# WBD_01.net
KiCad netlist of a schematic drawn in EAGLE
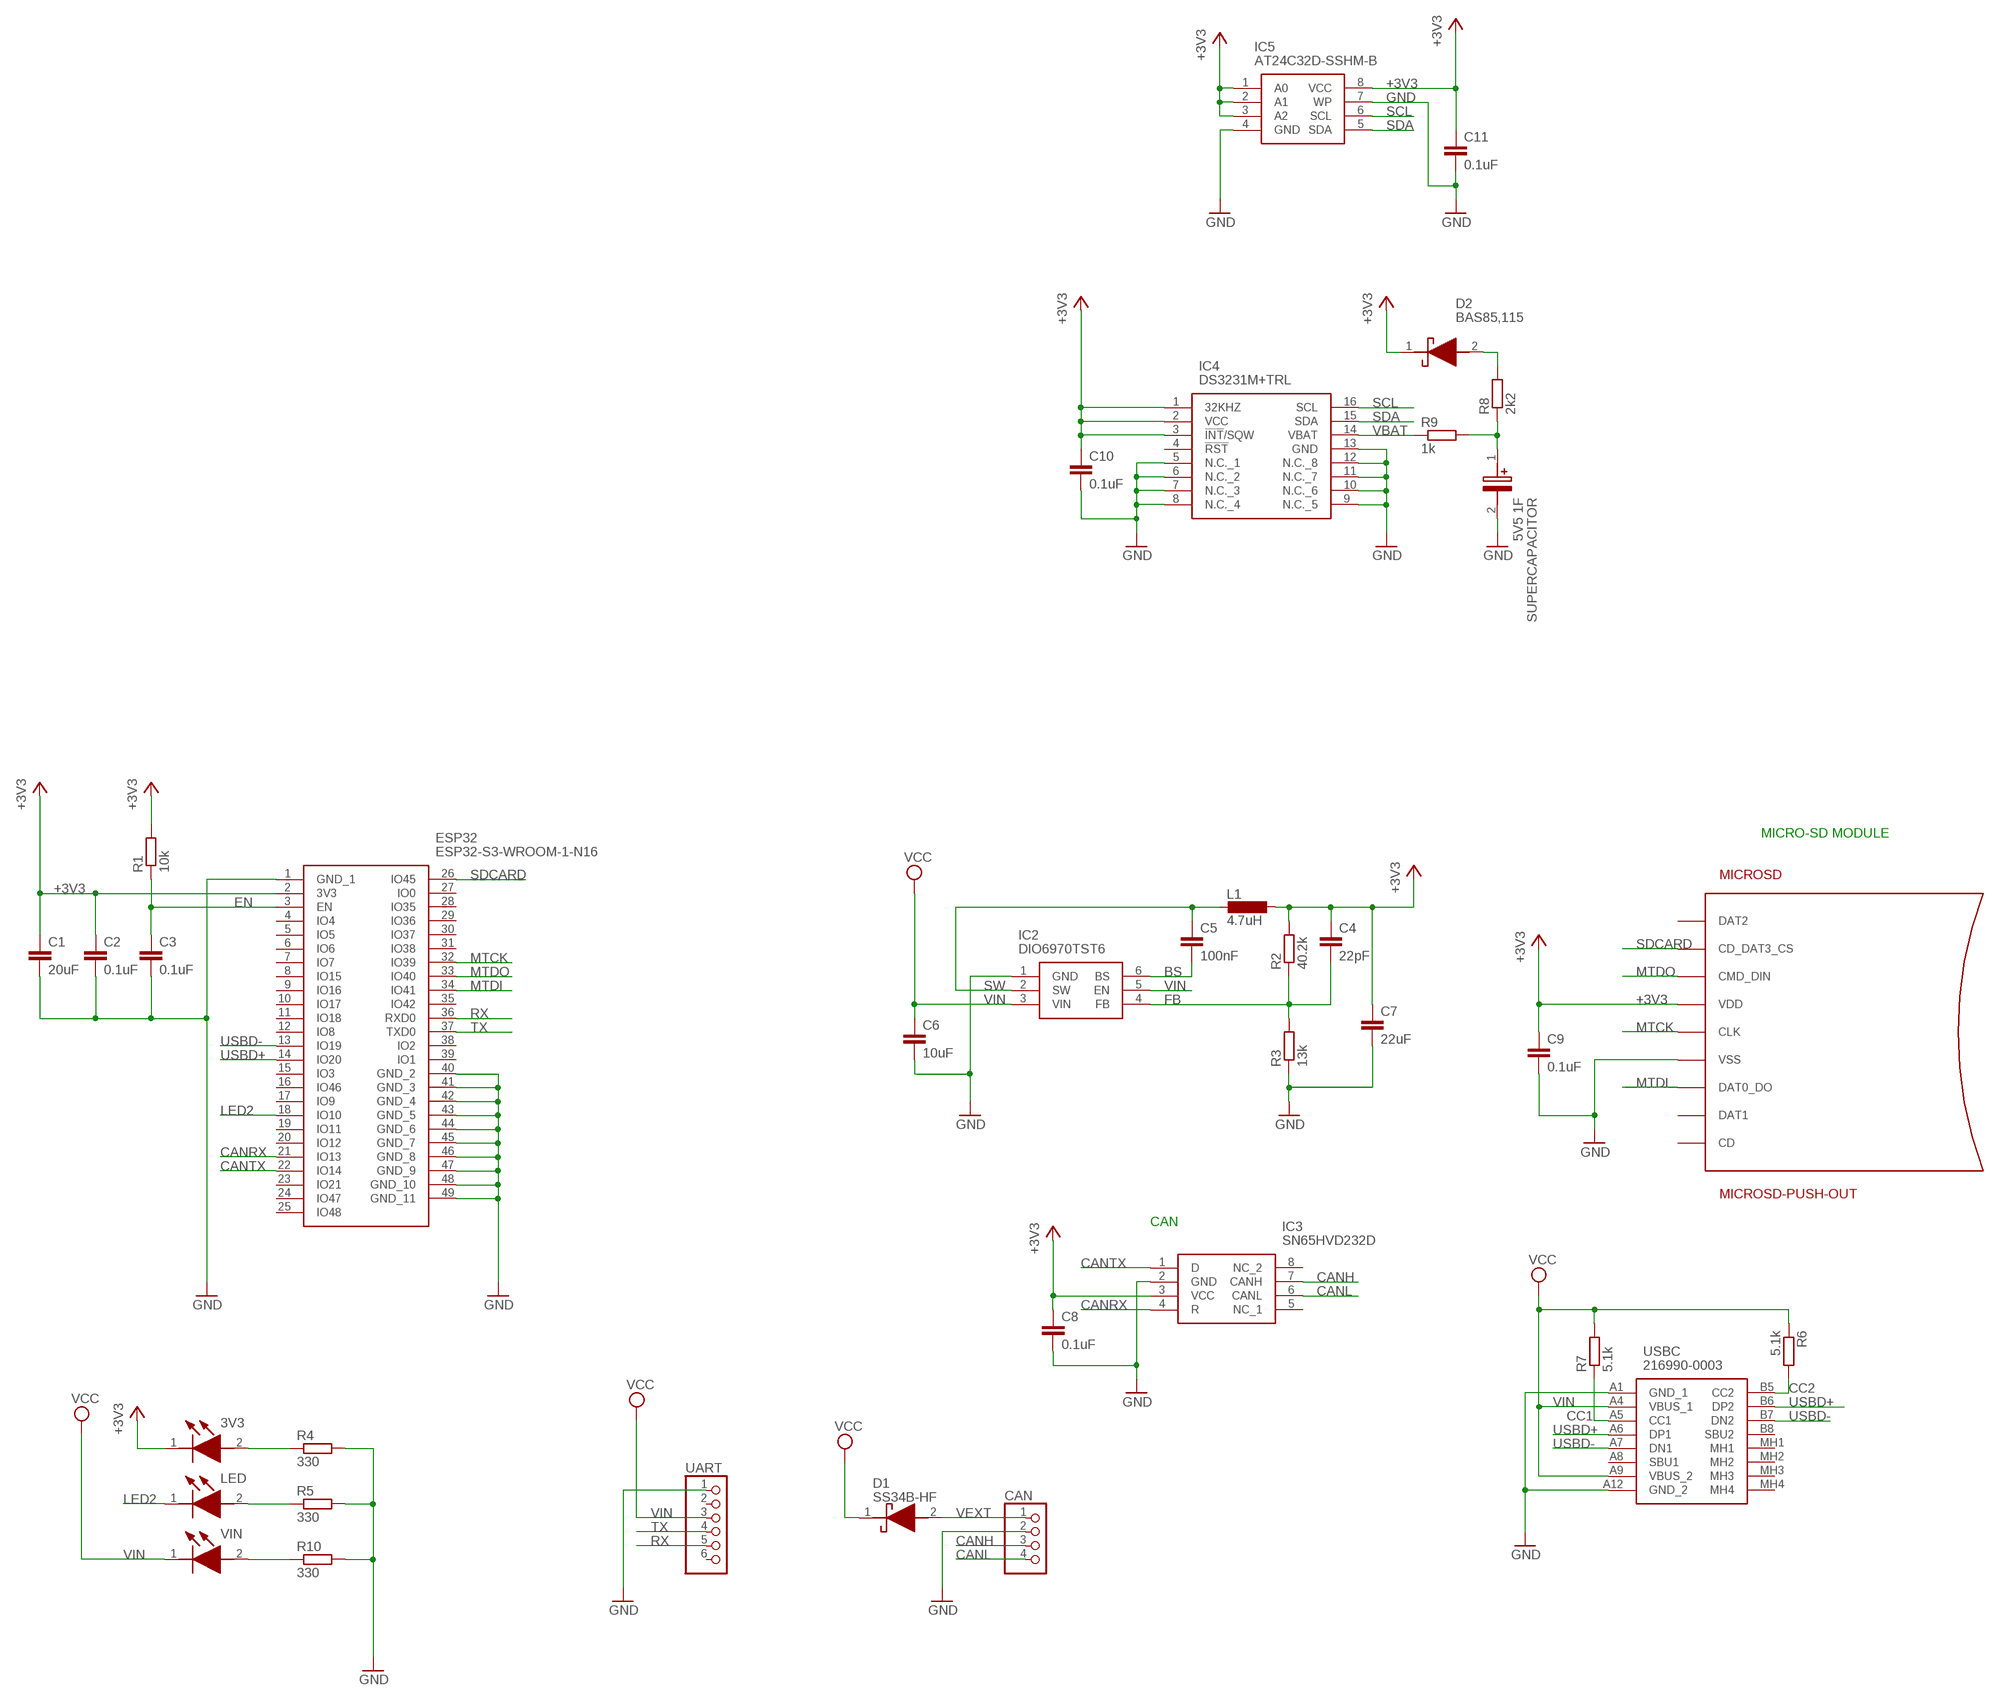
[diagram p0: schematic, sheet 1]

(export (version "E")
  (design (tool "Eeschema 10.0.6"))
  (components
    (comp (ref "3V3")
      (value "150060GS75000")
      (footprint "eagle-import:LEDC1608X80N")
      (fields (field (name "MOUSER_PART_NUMBER") "710-150060GS75000"))
      (libsource (lib "eagle-import") (part "150060GS75000"))
    )
    (comp (ref "C1")
      (value "20uF")
      (footprint "eagle-import:C0603")
      (libsource (lib "eagle-import") (part "C-EUC0603"))
    )
    (comp (ref "C2")
      (value "0.1uF")
      (footprint "eagle-import:C0603")
      (libsource (lib "eagle-import") (part "C-EUC0603"))
    )
    (comp (ref "C3")
      (value "0.1uF")
      (footprint "eagle-import:C0603")
      (libsource (lib "eagle-import") (part "C-EUC0603"))
    )
    (comp (ref "C4")
      (value "22pF")
      (footprint "eagle-import:C0603")
      (libsource (lib "eagle-import") (part "C-EUC0603"))
    )
    (comp (ref "C5")
      (value "100nF")
      (footprint "eagle-import:C0603")
      (libsource (lib "eagle-import") (part "C-EUC0603"))
    )
    (comp (ref "C6")
      (value "10uF")
      (footprint "eagle-import:C0603")
      (libsource (lib "eagle-import") (part "C-EUC0603"))
    )
    (comp (ref "C7")
      (value "22uF")
      (footprint "eagle-import:C0603")
      (libsource (lib "eagle-import") (part "C-EUC0603"))
    )
    (comp (ref "C8")
      (value "0.1uF")
      (footprint "eagle-import:C0603")
      (libsource (lib "eagle-import") (part "C-EUC0603"))
    )
    (comp (ref "C9")
      (value "0.1uF")
      (footprint "eagle-import:C0603")
      (libsource (lib "eagle-import") (part "C-EUC0603"))
    )
    (comp (ref "C10")
      (value "0.1uF")
      (footprint "eagle-import:C0603")
      (libsource (lib "eagle-import") (part "C-EUC0603"))
    )
    (comp (ref "C11")
      (value "0.1uF")
      (footprint "eagle-import:C0603")
      (libsource (lib "eagle-import") (part "C-EUC0603"))
    )
    (comp (ref "CAN")
      (value "PINHD-1X4M")
      (footprint "eagle-import:1X04M")
      (libsource (lib "eagle-import") (part "PINHD-1X4M"))
    )
    (comp (ref "D1")
      (value "SS34B-HF")
      (footprint "eagle-import:DIOM5336X320N")
      (fields (field (name "MOUSER_PART_NUMBER") "750-SS34B-HF"))
      (libsource (lib "eagle-import") (part "SS34B-HF"))
    )
    (comp (ref "D2")
      (value "BAS85,115")
      (footprint "eagle-import:BAS85115")
      (fields (field (name "MOUSER_PART_NUMBER") "771-BAS85-T/R"))
      (libsource (lib "eagle-import") (part "BAS85,115"))
    )
    (comp (ref "ESP32")
      (value "ESP32-S3-WROOM-1-N16")
      (footprint "eagle-import:ESP32S3WROOM1N16")
      (fields (field (name "MOUSER_PART_NUMBER") "356-ESP32S3WROOM1N16"))
      (libsource (lib "eagle-import") (part "ESP32-S3-WROOM-1-N16"))
    )
    (comp (ref "IC2")
      (value "DIO6970TST6")
      (footprint "eagle-import:SOT95P280X90-6N")
      (fields (field (name "MOUSER_PART_NUMBER") "453-DIO6970ST6"))
      (libsource (lib "eagle-import") (part "DIO6970TST6"))
    )
    (comp (ref "IC3")
      (value "SN65HVD232D")
      (footprint "eagle-import:SOIC127P600X175-8N")
      (fields (field (name "MOUSER_PART_NUMBER") "595-SN65HVD232D"))
      (libsource (lib "eagle-import") (part "SN65HVD232D"))
    )
    (comp (ref "IC4")
      (value "DS3231M+TRL")
      (footprint "eagle-import:SOIC127P1032X265-16N")
      (fields (field (name "MOUSER_PART_NUMBER") "700-DS3231M+TRL"))
      (libsource (lib "eagle-import") (part "DS3231M+TRL"))
    )
    (comp (ref "IC5")
      (value "AT24C32D-SSHM-B")
      (footprint "eagle-import:SOIC127P600X175-8N")
      (fields (field (name "MOUSER_PART_NUMBER") "556-AT24C32D-SSHM-B"))
      (libsource (lib "eagle-import") (part "AT24C32D-SSHM-B"))
    )
    (comp (ref "L1")
      (value "4.7uH")
      (footprint "eagle-import:L5650M")
      (libsource (lib "eagle-import") (part "L-EUL5650M"))
    )
    (comp (ref "LED")
      (value "150060GS75000")
      (footprint "eagle-import:LEDC1608X80N")
      (fields (field (name "MOUSER_PART_NUMBER") "710-150060GS75000"))
      (libsource (lib "eagle-import") (part "150060GS75000"))
    )
    (comp (ref "MICROSD")
      (value "MICROSD-PUSH-OUT")
      (footprint "eagle-import:MICROSD-PUSH-OUT")
      (libsource (lib "eagle-import") (part "MICROSD-PUSH-OUT"))
    )
    (comp (ref "R1")
      (value "10k")
      (footprint "eagle-import:R0603")
      (libsource (lib "eagle-import") (part "R-EU_R0603"))
    )
    (comp (ref "R2")
      (value "40.2k")
      (footprint "eagle-import:R0603")
      (libsource (lib "eagle-import") (part "R-EU_R0603"))
    )
    (comp (ref "R3")
      (value "13k")
      (footprint "eagle-import:R0603")
      (libsource (lib "eagle-import") (part "R-EU_R0603"))
    )
    (comp (ref "R4")
      (value "330")
      (footprint "eagle-import:R0603")
      (libsource (lib "eagle-import") (part "R-EU_R0603"))
    )
    (comp (ref "R5")
      (value "330")
      (footprint "eagle-import:R0603")
      (libsource (lib "eagle-import") (part "R-EU_R0603"))
    )
    (comp (ref "R6")
      (value "5.1k")
      (footprint "eagle-import:R0603")
      (libsource (lib "eagle-import") (part "R-EU_R0603"))
    )
    (comp (ref "R7")
      (value "5.1k")
      (footprint "eagle-import:R0603")
      (libsource (lib "eagle-import") (part "R-EU_R0603"))
    )
    (comp (ref "R8")
      (value "2k2")
      (footprint "eagle-import:R0603")
      (libsource (lib "eagle-import") (part "R-EU_R0603"))
    )
    (comp (ref "R9")
      (value "1k")
      (footprint "eagle-import:R0603")
      (libsource (lib "eagle-import") (part "R-EU_R0603"))
    )
    (comp (ref "R10")
      (value "330")
      (footprint "eagle-import:R0603")
      (libsource (lib "eagle-import") (part "R-EU_R0603"))
    )
    (comp (ref "SUPERCAPACITOR")
      (value "5V5 1F")
      (footprint "eagle-import:CAPPRD500W130D2150H800")
      (fields
        (field (name "MANUFACTURER_PART_NUMBER") "DB-5R5D105T")
        (field (name "MOUSER_PART_NUMBER") "555-DB-5R5D105T")
      )
      (libsource (lib "eagle-import") (part "DB-5R5D105T"))
    )
    (comp (ref "UART")
      (value "PINHD-1X6M")
      (footprint "eagle-import:1X06M")
      (libsource (lib "eagle-import") (part "PINHD-1X6M"))
    )
    (comp (ref "USBC")
      (value "216990-0003")
      (footprint "eagle-import:2169900003")
      (fields (field (name "MOUSER_PART_NUMBER") "538-216990-0003"))
      (libsource (lib "eagle-import") (part "216990-0003"))
    )
    (comp (ref "VIN")
      (value "150060GS75000")
      (footprint "eagle-import:LEDC1608X80N")
      (fields (field (name "MOUSER_PART_NUMBER") "710-150060GS75000"))
      (libsource (lib "eagle-import") (part "150060GS75000"))
    )
  )
  (nets
    (net (code "1") (name "+3V3") (class "Default")
      (node (ref "3V3") (pin "1") (pinfunction "K_1") (pintype "bidirectional"))
      (node (ref "C1") (pin "1") (pinfunction "1_1") (pintype "passive"))
      (node (ref "C10") (pin "1") (pinfunction "1_1") (pintype "passive"))
      (node (ref "C11") (pin "1") (pinfunction "1_1") (pintype "passive"))
      (node (ref "C2") (pin "1") (pinfunction "1_1") (pintype "passive"))
      (node (ref "C4") (pin "1") (pinfunction "1_1") (pintype "passive"))
      (node (ref "C7") (pin "1") (pinfunction "1_1") (pintype "passive"))
      (node (ref "C8") (pin "1") (pinfunction "1_1") (pintype "passive"))
      (node (ref "C9") (pin "1") (pinfunction "1_1") (pintype "passive"))
      (node (ref "D2") (pin "1") (pinfunction "K_1") (pintype "bidirectional"))
      (node (ref "ESP32") (pin "2") (pinfunction "3V3_2") (pintype "bidirectional"))
      (node (ref "IC3") (pin "3") (pinfunction "VCC_3") (pintype "bidirectional"))
      (node (ref "IC4") (pin "1") (pinfunction "32KHZ_1") (pintype "bidirectional"))
      (node (ref "IC4") (pin "2") (pinfunction "VCC_2") (pintype "bidirectional"))
      (node (ref "IC4") (pin "3") (pinfunction "~{INT}/SQW_3") (pintype "bidirectional"))
      (node (ref "IC5") (pin "1") (pinfunction "A0_1") (pintype "bidirectional"))
      (node (ref "IC5") (pin "2") (pinfunction "A1_2") (pintype "bidirectional"))
      (node (ref "IC5") (pin "3") (pinfunction "A2_3") (pintype "bidirectional"))
      (node (ref "IC5") (pin "8") (pinfunction "VCC_8") (pintype "bidirectional"))
      (node (ref "L1") (pin "1") (pinfunction "1_1") (pintype "passive"))
      (node (ref "MICROSD") (pin "4") (pinfunction "VDD_4") (pintype "bidirectional"))
      (node (ref "R1") (pin "2") (pinfunction "2_2") (pintype "passive"))
      (node (ref "R2") (pin "2") (pinfunction "2_2") (pintype "passive"))
    )
    (net (code "2") (name "/BS") (class "Default")
      (node (ref "C5") (pin "2") (pinfunction "2_2") (pintype "passive"))
      (node (ref "IC2") (pin "6") (pinfunction "BS_6") (pintype "bidirectional"))
    )
    (net (code "3") (name "/CANH") (class "Default")
      (node (ref "CAN") (pin "3") (pinfunction "3_3") (pintype "passive"))
      (node (ref "IC3") (pin "7") (pinfunction "CANH_7") (pintype "bidirectional"))
    )
    (net (code "4") (name "/CANL") (class "Default")
      (node (ref "CAN") (pin "4") (pinfunction "4_4") (pintype "passive"))
      (node (ref "IC3") (pin "6") (pinfunction "CANL_6") (pintype "bidirectional"))
    )
    (net (code "5") (name "/CANRX") (class "Default")
      (node (ref "ESP32") (pin "21") (pinfunction "IO13_21") (pintype "bidirectional"))
      (node (ref "IC3") (pin "4") (pinfunction "R_4") (pintype "bidirectional"))
    )
    (net (code "6") (name "/CANTX") (class "Default")
      (node (ref "ESP32") (pin "22") (pinfunction "IO14_22") (pintype "bidirectional"))
      (node (ref "IC3") (pin "1") (pinfunction "D_1") (pintype "bidirectional"))
    )
    (net (code "7") (name "/CC1") (class "Default")
      (node (ref "R7") (pin "1") (pinfunction "1_1") (pintype "passive"))
      (node (ref "USBC") (pin "A5") (pinfunction "CC1_A5") (pintype "bidirectional"))
    )
    (net (code "8") (name "/CC2") (class "Default")
      (node (ref "R6") (pin "2") (pinfunction "2_2") (pintype "passive"))
      (node (ref "USBC") (pin "B5") (pinfunction "CC2_B5") (pintype "bidirectional"))
    )
    (net (code "9") (name "/EN") (class "Default")
      (node (ref "C3") (pin "1") (pinfunction "1_1") (pintype "passive"))
      (node (ref "ESP32") (pin "3") (pinfunction "EN_3") (pintype "bidirectional"))
      (node (ref "R1") (pin "1") (pinfunction "1_1") (pintype "passive"))
    )
    (net (code "10") (name "/FB") (class "Default")
      (node (ref "C4") (pin "2") (pinfunction "2_2") (pintype "passive"))
      (node (ref "IC2") (pin "4") (pinfunction "FB_4") (pintype "bidirectional"))
      (node (ref "R2") (pin "1") (pinfunction "1_1") (pintype "passive"))
      (node (ref "R3") (pin "2") (pinfunction "2_2") (pintype "passive"))
    )
    (net (code "11") (name "/LED2") (class "Default")
      (node (ref "ESP32") (pin "18") (pinfunction "IO10_18") (pintype "bidirectional"))
      (node (ref "LED") (pin "1") (pinfunction "K_1") (pintype "bidirectional"))
    )
    (net (code "12") (name "/MTCK") (class "Default")
      (node (ref "ESP32") (pin "32") (pinfunction "IO39_32") (pintype "bidirectional"))
      (node (ref "MICROSD") (pin "5") (pinfunction "CLK_5") (pintype "bidirectional"))
    )
    (net (code "13") (name "/MTDI") (class "Default")
      (node (ref "ESP32") (pin "34") (pinfunction "IO41_34") (pintype "bidirectional"))
      (node (ref "MICROSD") (pin "7") (pinfunction "DAT0_DO_7") (pintype "bidirectional"))
    )
    (net (code "14") (name "/MTDO") (class "Default")
      (node (ref "ESP32") (pin "33") (pinfunction "IO40_33") (pintype "bidirectional"))
      (node (ref "MICROSD") (pin "3") (pinfunction "CMD_DIN_3") (pintype "bidirectional"))
    )
    (net (code "15") (name "/RX") (class "Default")
      (node (ref "ESP32") (pin "36") (pinfunction "RXD0_36") (pintype "bidirectional"))
      (node (ref "UART") (pin "5") (pinfunction "5_5") (pintype "passive"))
    )
    (net (code "16") (name "/SCL") (class "Default")
      (node (ref "IC4") (pin "16") (pinfunction "SCL_16") (pintype "bidirectional"))
      (node (ref "IC5") (pin "6") (pinfunction "SCL_6") (pintype "bidirectional"))
    )
    (net (code "17") (name "/SDA") (class "Default")
      (node (ref "IC4") (pin "15") (pinfunction "SDA_15") (pintype "bidirectional"))
      (node (ref "IC5") (pin "5") (pinfunction "SDA_5") (pintype "bidirectional"))
    )
    (net (code "18") (name "/SDCARD") (class "Default")
      (node (ref "ESP32") (pin "26") (pinfunction "IO45_26") (pintype "bidirectional"))
      (node (ref "MICROSD") (pin "2") (pinfunction "CD_DAT3_CS_2") (pintype "bidirectional"))
    )
    (net (code "19") (name "/SW") (class "Default")
      (node (ref "C5") (pin "1") (pinfunction "1_1") (pintype "passive"))
      (node (ref "IC2") (pin "2") (pinfunction "SW_2") (pintype "bidirectional"))
      (node (ref "L1") (pin "2") (pinfunction "2_2") (pintype "passive"))
    )
    (net (code "20") (name "/TX") (class "Default")
      (node (ref "ESP32") (pin "37") (pinfunction "TXD0_37") (pintype "bidirectional"))
      (node (ref "UART") (pin "4") (pinfunction "4_4") (pintype "passive"))
    )
    (net (code "21") (name "/USBD+") (class "Default")
      (node (ref "ESP32") (pin "14") (pinfunction "IO20_14") (pintype "bidirectional"))
      (node (ref "USBC") (pin "A6") (pinfunction "DP1_A6") (pintype "bidirectional"))
      (node (ref "USBC") (pin "B6") (pinfunction "DP2_B6") (pintype "bidirectional"))
    )
    (net (code "22") (name "/USBD-") (class "Default")
      (node (ref "ESP32") (pin "13") (pinfunction "IO19_13") (pintype "bidirectional"))
      (node (ref "USBC") (pin "A7") (pinfunction "DN1_A7") (pintype "bidirectional"))
      (node (ref "USBC") (pin "B7") (pinfunction "DN2_B7") (pintype "bidirectional"))
    )
    (net (code "23") (name "/VBAT") (class "Default")
      (node (ref "IC4") (pin "14") (pinfunction "VBAT_14") (pintype "bidirectional"))
      (node (ref "R9") (pin "1") (pinfunction "1_1") (pintype "passive"))
    )
    (net (code "24") (name "/VEXT") (class "Default")
      (node (ref "CAN") (pin "1") (pinfunction "1_1") (pintype "passive"))
      (node (ref "D1") (pin "2") (pinfunction "A_2") (pintype "bidirectional"))
    )
    (net (code "25") (name "GND") (class "Default")
      (node (ref "C1") (pin "2") (pinfunction "2_2") (pintype "passive"))
      (node (ref "C10") (pin "2") (pinfunction "2_2") (pintype "passive"))
      (node (ref "C11") (pin "2") (pinfunction "2_2") (pintype "passive"))
      (node (ref "C2") (pin "2") (pinfunction "2_2") (pintype "passive"))
      (node (ref "C3") (pin "2") (pinfunction "2_2") (pintype "passive"))
      (node (ref "C6") (pin "2") (pinfunction "2_2") (pintype "passive"))
      (node (ref "C7") (pin "2") (pinfunction "2_2") (pintype "passive"))
      (node (ref "C8") (pin "2") (pinfunction "2_2") (pintype "passive"))
      (node (ref "C9") (pin "2") (pinfunction "2_2") (pintype "passive"))
      (node (ref "CAN") (pin "2") (pinfunction "2_2") (pintype "passive"))
      (node (ref "ESP32") (pin "1") (pinfunction "GND_1_1") (pintype "bidirectional"))
      (node (ref "ESP32") (pin "40") (pinfunction "GND_2_40") (pintype "bidirectional"))
      (node (ref "ESP32") (pin "41") (pinfunction "GND_3_41") (pintype "bidirectional"))
      (node (ref "ESP32") (pin "42") (pinfunction "GND_4_42") (pintype "bidirectional"))
      (node (ref "ESP32") (pin "43") (pinfunction "GND_5_43") (pintype "bidirectional"))
      (node (ref "ESP32") (pin "44") (pinfunction "GND_6_44") (pintype "bidirectional"))
      (node (ref "ESP32") (pin "45") (pinfunction "GND_7_45") (pintype "bidirectional"))
      (node (ref "ESP32") (pin "46") (pinfunction "GND_8_46") (pintype "bidirectional"))
      (node (ref "ESP32") (pin "47") (pinfunction "GND_9_47") (pintype "bidirectional"))
      (node (ref "ESP32") (pin "48") (pinfunction "GND_10_48") (pintype "bidirectional"))
      (node (ref "ESP32") (pin "49") (pinfunction "GND_11_49") (pintype "bidirectional"))
      (node (ref "IC2") (pin "1") (pinfunction "GND_1") (pintype "bidirectional"))
      (node (ref "IC3") (pin "2") (pinfunction "GND_2") (pintype "bidirectional"))
      (node (ref "IC4") (pin "10") (pinfunction "N.C._6_10") (pintype "bidirectional"))
      (node (ref "IC4") (pin "11") (pinfunction "N.C._7_11") (pintype "bidirectional"))
      (node (ref "IC4") (pin "12") (pinfunction "N.C._8_12") (pintype "bidirectional"))
      (node (ref "IC4") (pin "13") (pinfunction "GND_13") (pintype "bidirectional"))
      (node (ref "IC4") (pin "5") (pinfunction "N.C._1_5") (pintype "bidirectional"))
      (node (ref "IC4") (pin "6") (pinfunction "N.C._2_6") (pintype "bidirectional"))
      (node (ref "IC4") (pin "7") (pinfunction "N.C._3_7") (pintype "bidirectional"))
      (node (ref "IC4") (pin "8") (pinfunction "N.C._4_8") (pintype "bidirectional"))
      (node (ref "IC4") (pin "9") (pinfunction "N.C._5_9") (pintype "bidirectional"))
      (node (ref "IC5") (pin "4") (pinfunction "GND_4") (pintype "bidirectional"))
      (node (ref "IC5") (pin "7") (pinfunction "WP_7") (pintype "bidirectional"))
      (node (ref "MICROSD") (pin "6") (pinfunction "VSS_6") (pintype "bidirectional"))
      (node (ref "MICROSD") (pin "G1") (pinfunction "VSS_G1") (pintype "bidirectional"))
      (node (ref "MICROSD") (pin "G2") (pinfunction "VSS_G2") (pintype "bidirectional"))
      (node (ref "MICROSD") (pin "G3") (pinfunction "VSS_G3") (pintype "bidirectional"))
      (node (ref "MICROSD") (pin "G4") (pinfunction "VSS_G4") (pintype "bidirectional"))
      (node (ref "R10") (pin "2") (pinfunction "2_2") (pintype "passive"))
      (node (ref "R3") (pin "1") (pinfunction "1_1") (pintype "passive"))
      (node (ref "R4") (pin "2") (pinfunction "2_2") (pintype "passive"))
      (node (ref "R5") (pin "2") (pinfunction "2_2") (pintype "passive"))
      (node (ref "SUPERCAPACITOR") (pin "2") (pinfunction "-_2") (pintype "bidirectional"))
      (node (ref "UART") (pin "1") (pinfunction "1_1") (pintype "passive"))
      (node (ref "USBC") (pin "A1") (pinfunction "GND_1_A1") (pintype "bidirectional"))
      (node (ref "USBC") (pin "A12") (pinfunction "GND_2_A12") (pintype "bidirectional"))
    )
    (net (code "26") (name "Net-(3V3-A)") (class "Default")
      (node (ref "3V3") (pin "2") (pinfunction "A_2") (pintype "bidirectional"))
      (node (ref "R4") (pin "1") (pinfunction "1_1") (pintype "passive"))
    )
    (net (code "27") (name "Net-(D2-A)") (class "Default")
      (node (ref "D2") (pin "2") (pinfunction "A_2") (pintype "bidirectional"))
      (node (ref "R8") (pin "2") (pinfunction "2_2") (pintype "passive"))
    )
    (net (code "28") (name "Net-(LED-A)") (class "Default")
      (node (ref "LED") (pin "2") (pinfunction "A_2") (pintype "bidirectional"))
      (node (ref "R5") (pin "1") (pinfunction "1_1") (pintype "passive"))
    )
    (net (code "29") (name "Net-(SUPERCAPACITOR-+)") (class "Default")
      (node (ref "R8") (pin "1") (pinfunction "1_1") (pintype "passive"))
      (node (ref "R9") (pin "2") (pinfunction "2_2") (pintype "passive"))
      (node (ref "SUPERCAPACITOR") (pin "1") (pinfunction "+_1") (pintype "bidirectional"))
    )
    (net (code "30") (name "Net-(VIN-A)") (class "Default")
      (node (ref "R10") (pin "1") (pinfunction "1_1") (pintype "passive"))
      (node (ref "VIN") (pin "2") (pinfunction "A_2") (pintype "bidirectional"))
    )
    (net (code "31") (name "VCC") (class "Default")
      (node (ref "C6") (pin "1") (pinfunction "1_1") (pintype "passive"))
      (node (ref "D1") (pin "1") (pinfunction "K_1") (pintype "bidirectional"))
      (node (ref "IC2") (pin "3") (pinfunction "VIN_3") (pintype "bidirectional"))
      (node (ref "IC2") (pin "5") (pinfunction "EN_5") (pintype "bidirectional"))
      (node (ref "R6") (pin "1") (pinfunction "1_1") (pintype "passive"))
      (node (ref "R7") (pin "2") (pinfunction "2_2") (pintype "passive"))
      (node (ref "UART") (pin "3") (pinfunction "3_3") (pintype "passive"))
      (node (ref "USBC") (pin "A4") (pinfunction "VBUS_1_A4") (pintype "bidirectional"))
      (node (ref "USBC") (pin "A9") (pinfunction "VBUS_2_A9") (pintype "bidirectional"))
      (node (ref "VIN") (pin "1") (pinfunction "K_1") (pintype "bidirectional"))
    )
    (net (code "32") (name "unconnected-(ESP32-IO0-Pad27)") (class "Default")
      (node (ref "ESP32") (pin "27") (pinfunction "IO0_27") (pintype "bidirectional"))
    )
    (net (code "33") (name "unconnected-(ESP32-IO1-Pad39)") (class "Default")
      (node (ref "ESP32") (pin "39") (pinfunction "IO1_39") (pintype "bidirectional"))
    )
    (net (code "34") (name "unconnected-(ESP32-IO2-Pad38)") (class "Default")
      (node (ref "ESP32") (pin "38") (pinfunction "IO2_38") (pintype "bidirectional"))
    )
    (net (code "35") (name "unconnected-(ESP32-IO3-Pad15)") (class "Default")
      (node (ref "ESP32") (pin "15") (pinfunction "IO3_15") (pintype "bidirectional"))
    )
    (net (code "36") (name "unconnected-(ESP32-IO4-Pad4)") (class "Default")
      (node (ref "ESP32") (pin "4") (pinfunction "IO4_4") (pintype "bidirectional"))
    )
    (net (code "37") (name "unconnected-(ESP32-IO5-Pad5)") (class "Default")
      (node (ref "ESP32") (pin "5") (pinfunction "IO5_5") (pintype "bidirectional"))
    )
    (net (code "38") (name "unconnected-(ESP32-IO6-Pad6)") (class "Default")
      (node (ref "ESP32") (pin "6") (pinfunction "IO6_6") (pintype "bidirectional"))
    )
    (net (code "39") (name "unconnected-(ESP32-IO7-Pad7)") (class "Default")
      (node (ref "ESP32") (pin "7") (pinfunction "IO7_7") (pintype "bidirectional"))
    )
    (net (code "40") (name "unconnected-(ESP32-IO8-Pad12)") (class "Default")
      (node (ref "ESP32") (pin "12") (pinfunction "IO8_12") (pintype "bidirectional"))
    )
    (net (code "41") (name "unconnected-(ESP32-IO9-Pad17)") (class "Default")
      (node (ref "ESP32") (pin "17") (pinfunction "IO9_17") (pintype "bidirectional"))
    )
    (net (code "42") (name "unconnected-(ESP32-IO11-Pad19)") (class "Default")
      (node (ref "ESP32") (pin "19") (pinfunction "IO11_19") (pintype "bidirectional"))
    )
    (net (code "43") (name "unconnected-(ESP32-IO12-Pad20)") (class "Default")
      (node (ref "ESP32") (pin "20") (pinfunction "IO12_20") (pintype "bidirectional"))
    )
    (net (code "44") (name "unconnected-(ESP32-IO15-Pad8)") (class "Default")
      (node (ref "ESP32") (pin "8") (pinfunction "IO15_8") (pintype "bidirectional"))
    )
    (net (code "45") (name "unconnected-(ESP32-IO16-Pad9)") (class "Default")
      (node (ref "ESP32") (pin "9") (pinfunction "IO16_9") (pintype "bidirectional"))
    )
    (net (code "46") (name "unconnected-(ESP32-IO17-Pad10)") (class "Default")
      (node (ref "ESP32") (pin "10") (pinfunction "IO17_10") (pintype "bidirectional"))
    )
    (net (code "47") (name "unconnected-(ESP32-IO18-Pad11)") (class "Default")
      (node (ref "ESP32") (pin "11") (pinfunction "IO18_11") (pintype "bidirectional"))
    )
    (net (code "48") (name "unconnected-(ESP32-IO21-Pad23)") (class "Default")
      (node (ref "ESP32") (pin "23") (pinfunction "IO21_23") (pintype "bidirectional"))
    )
    (net (code "49") (name "unconnected-(ESP32-IO35-Pad28)") (class "Default")
      (node (ref "ESP32") (pin "28") (pinfunction "IO35_28") (pintype "bidirectional"))
    )
    (net (code "50") (name "unconnected-(ESP32-IO36-Pad29)") (class "Default")
      (node (ref "ESP32") (pin "29") (pinfunction "IO36_29") (pintype "bidirectional"))
    )
    (net (code "51") (name "unconnected-(ESP32-IO37-Pad30)") (class "Default")
      (node (ref "ESP32") (pin "30") (pinfunction "IO37_30") (pintype "bidirectional"))
    )
    (net (code "52") (name "unconnected-(ESP32-IO38-Pad31)") (class "Default")
      (node (ref "ESP32") (pin "31") (pinfunction "IO38_31") (pintype "bidirectional"))
    )
    (net (code "53") (name "unconnected-(ESP32-IO42-Pad35)") (class "Default")
      (node (ref "ESP32") (pin "35") (pinfunction "IO42_35") (pintype "bidirectional"))
    )
    (net (code "54") (name "unconnected-(ESP32-IO46-Pad16)") (class "Default")
      (node (ref "ESP32") (pin "16") (pinfunction "IO46_16") (pintype "bidirectional"))
    )
    (net (code "55") (name "unconnected-(ESP32-IO47-Pad24)") (class "Default")
      (node (ref "ESP32") (pin "24") (pinfunction "IO47_24") (pintype "bidirectional"))
    )
    (net (code "56") (name "unconnected-(ESP32-IO48-Pad25)") (class "Default")
      (node (ref "ESP32") (pin "25") (pinfunction "IO48_25") (pintype "bidirectional"))
    )
    (net (code "57") (name "unconnected-(IC3-NC_1-Pad5)") (class "Default")
      (node (ref "IC3") (pin "5") (pinfunction "NC_1_5") (pintype "bidirectional"))
    )
    (net (code "58") (name "unconnected-(IC3-NC_2-Pad8)") (class "Default")
      (node (ref "IC3") (pin "8") (pinfunction "NC_2_8") (pintype "bidirectional"))
    )
    (net (code "59") (name "unconnected-(IC4-~{RST}-Pad4)") (class "Default")
      (node (ref "IC4") (pin "4") (pinfunction "~{RST}_4") (pintype "bidirectional"))
    )
    (net (code "60") (name "unconnected-(MICROSD-DAT1-Pad8)") (class "Default")
      (node (ref "MICROSD") (pin "8") (pinfunction "DAT1_8") (pintype "bidirectional"))
    )
    (net (code "61") (name "unconnected-(MICROSD-DAT2-Pad1)") (class "Default")
      (node (ref "MICROSD") (pin "1") (pinfunction "DAT2_1") (pintype "bidirectional"))
    )
    (net (code "62") (name "unconnected-(MICROSD-PadCD)") (class "Default")
      (node (ref "MICROSD") (pin "CD") (pinfunction "CD_CD") (pintype "bidirectional"))
    )
    (net (code "63") (name "unconnected-(UART-Pad2)") (class "Default")
      (node (ref "UART") (pin "2") (pinfunction "2_2") (pintype "passive"))
    )
    (net (code "64") (name "unconnected-(UART-Pad6)") (class "Default")
      (node (ref "UART") (pin "6") (pinfunction "6_6") (pintype "passive"))
    )
    (net (code "65") (name "unconnected-(USBC-PadMH1)") (class "Default")
      (node (ref "USBC") (pin "MH1") (pinfunction "MH1_MH1") (pintype "bidirectional"))
    )
    (net (code "66") (name "unconnected-(USBC-PadMH2)") (class "Default")
      (node (ref "USBC") (pin "MH2") (pinfunction "MH2_MH2") (pintype "bidirectional"))
    )
    (net (code "67") (name "unconnected-(USBC-PadMH3)") (class "Default")
      (node (ref "USBC") (pin "MH3") (pinfunction "MH3_MH3") (pintype "bidirectional"))
    )
    (net (code "68") (name "unconnected-(USBC-PadMH4)") (class "Default")
      (node (ref "USBC") (pin "MH4") (pinfunction "MH4_MH4") (pintype "bidirectional"))
    )
    (net (code "69") (name "unconnected-(USBC-SBU1-PadA8)") (class "Default")
      (node (ref "USBC") (pin "A8") (pinfunction "SBU1_A8") (pintype "bidirectional"))
    )
    (net (code "70") (name "unconnected-(USBC-SBU2-PadB8)") (class "Default")
      (node (ref "USBC") (pin "B8") (pinfunction "SBU2_B8") (pintype "bidirectional"))
    )
  )
)
